# IR_remote.net
KiCad netlist of a schematic drawn in Altium Designer
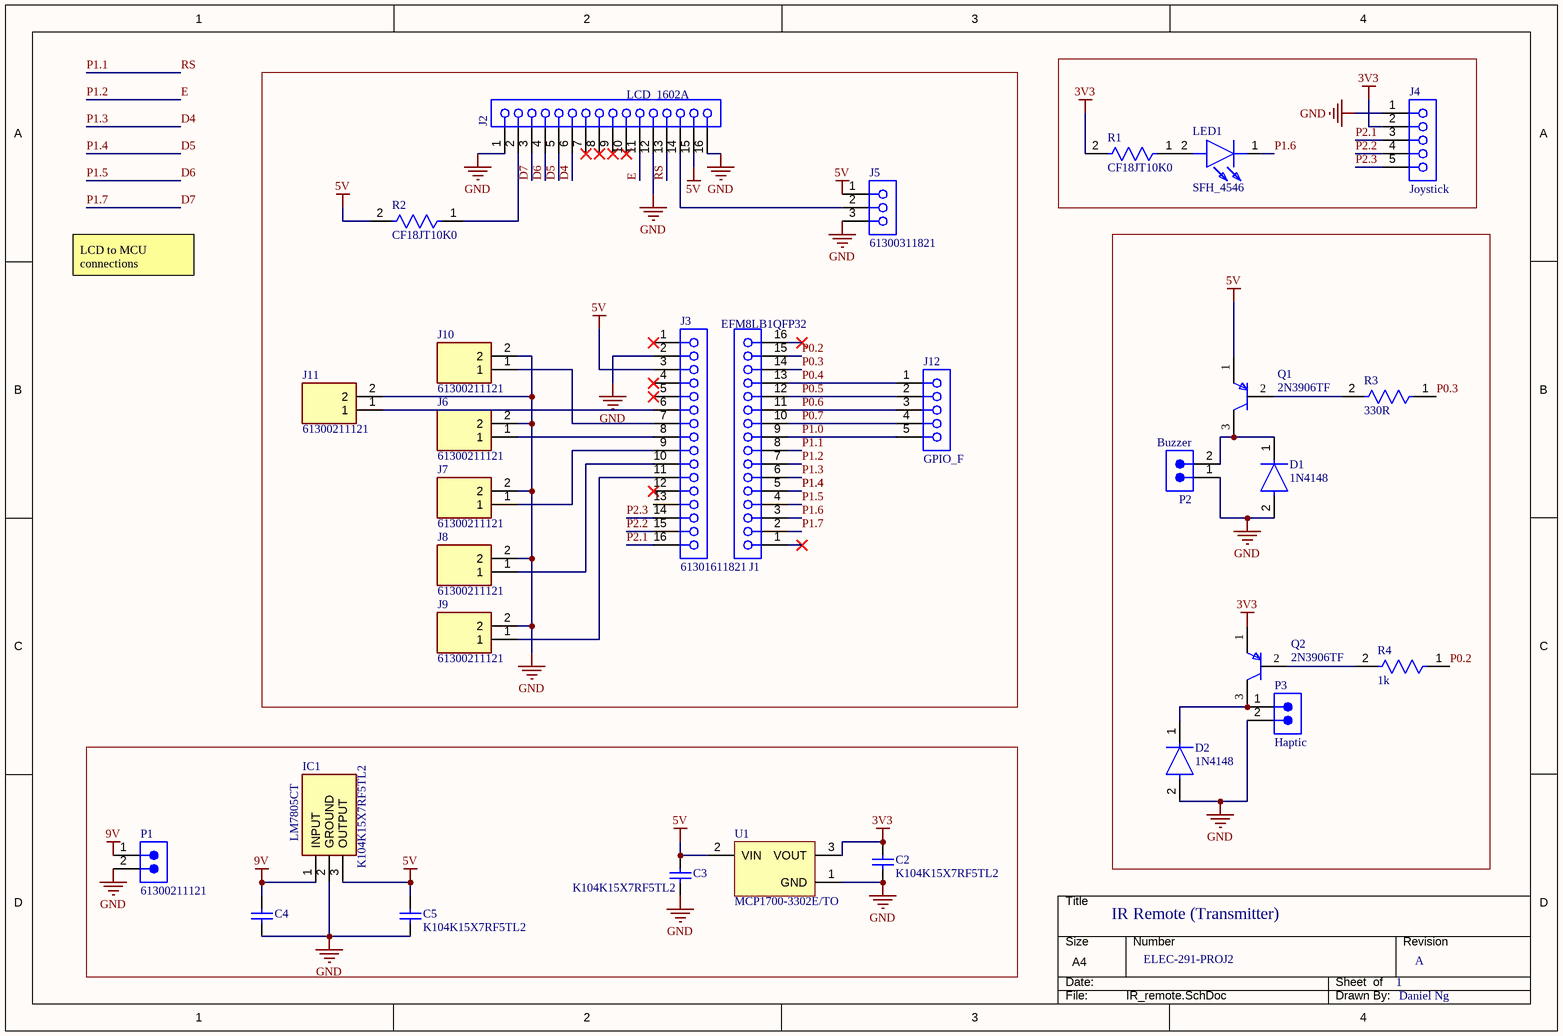
[diagram p0: IR_remote.SchDoc]

(export (version "E")
  (design (tool "Eeschema 10.0.6"))
  (components
    (comp (ref "C2")
      (value "K104K15X7RF5TL2")
      (footprint "VISH-K104K15X7RF5TL2")
      (description "Ceramic Capacitor, 100 nF, +/- 10%, 50 V, -55 to 125 degC, 2-Pin THD, RoHS, Tape and Reel")
      (fields (field (name "MANUFACTURER") "Vishay") (field (name "TOLERANCE") "±10%"))
      (libsource (lib "Altium Content Vault") (part "CAP-NP-2"))
    )
    (comp (ref "C3")
      (value "K104K15X7RF5TL2")
      (footprint "VISH-K104K15X7RF5TL2")
      (description "Ceramic Capacitor, 100 nF, +/- 10%, 50 V, -55 to 125 degC, 2-Pin THD, RoHS, Tape and Reel")
      (fields (field (name "MANUFACTURER") "Vishay") (field (name "TOLERANCE") "±10%"))
      (libsource (lib "Altium Content Vault") (part "CAP-NP-2"))
    )
    (comp (ref "C4")
      (value "K104K15X7RF5TL2")
      (footprint "VISH-K104K15X7RF5TL2")
      (description "Ceramic Capacitor, 100 nF, +/- 10%, 50 V, -55 to 125 degC, 2-Pin THD, RoHS, Tape and Reel")
      (fields (field (name "MANUFACTURER") "Vishay") (field (name "TOLERANCE") "±10%"))
      (libsource (lib "Altium Content Vault") (part "CAP-NP-2"))
    )
    (comp (ref "C5")
      (value "K104K15X7RF5TL2")
      (footprint "VISH-K104K15X7RF5TL2")
      (description "Ceramic Capacitor, 100 nF, +/- 10%, 50 V, -55 to 125 degC, 2-Pin THD, RoHS, Tape and Reel")
      (fields (field (name "MANUFACTURER") "Vishay") (field (name "TOLERANCE") "±10%"))
      (libsource (lib "Altium Content Vault") (part "CAP-NP-2"))
    )
    (comp (ref "D1")
      (value "1N4148")
      (footprint "FP-017AG-MFG")
      (description "DIODE GEN PURP 100V 200MA DO35")
      (fields (field (name "VOLTAGE") "100V"))
      (libsource (lib "Altium Content Vault") (part "d7152d700b627762746794eb795d46e"))
    )
    (comp (ref "D2")
      (value "1N4148")
      (footprint "FP-017AG-MFG")
      (description "DIODE GEN PURP 100V 200MA DO35")
      (fields (field (name "VOLTAGE") "100V"))
      (libsource (lib "Altium Content Vault") (part "d7152d700b627762746794eb795d46e"))
    )
    (comp (ref "IC1")
      (value "LM7805CT")
      (footprint "SamacSys:TO254P470X1028X1955-3P")
      (description "Integrated Circuit")
      (fields (field (name "MOUSER PART NUMBER") "926-LM7805CT"))
      (libsource (lib "*") (part "LM7805CT"))
    )
    (comp (ref "J1")
      (value "EFM8LB1QFP32")
      (footprint "61301611821")
      (description "THT Vertical Socket Header WR-PHD, Pitch 2.54 mm, Single Row, 16 pins")
      (libsource (lib "Altium Content Vault") (part "Header_Female_1R_16P"))
    )
    (comp (ref "J2")
      (value "LCD_1602A")
      (footprint "61301611821")
      (description "THT Vertical Socket Header WR-PHD, Pitch 2.54 mm, Single Row, 16 pins")
      (libsource (lib "Altium Content Vault") (part "Header_Female_1R_16P"))
    )
    (comp (ref "J3")
      (value "61301611821")
      (footprint "61301611821")
      (description "THT Vertical Socket Header WR-PHD, Pitch 2.54 mm, Single Row, 16 pins")
      (libsource (lib "Altium Content Vault") (part "Header_Female_1R_16P"))
    )
    (comp (ref "J4")
      (value "Joystick")
      (footprint "61300511821")
      (description "THT Vertical Socket Header WR-PHD, Pitch 2.54 mm, Single Row, 5 pins")
      (libsource (lib "Altium Content Vault") (part "Header_Female_1R_05P"))
    )
    (comp (ref "J5")
      (value "61300311821")
      (footprint "61300311821")
      (description "Btb Conn, Rcpt, 3Pos, 1Row, 2.54Mm Rohs Compliant: Yes")
      (libsource (lib "Altium Content Vault") (part "Header_Female_1R_03P"))
    )
    (comp (ref "J6")
      (value "61300211121")
      (footprint "SamacSys:HDRV2W110P0X254_1X2_508X254X854P")
      (description "Connector")
      (fields (field (name "MOUSER PART NUMBER") "710-61300211121"))
      (libsource (lib "*") (part "61300211121"))
    )
    (comp (ref "J7")
      (value "61300211121")
      (footprint "SamacSys:HDRV2W110P0X254_1X2_508X254X854P")
      (description "Connector")
      (fields (field (name "MOUSER PART NUMBER") "710-61300211121"))
      (libsource (lib "*") (part "61300211121"))
    )
    (comp (ref "J8")
      (value "61300211121")
      (footprint "SamacSys:HDRV2W110P0X254_1X2_508X254X854P")
      (description "Connector")
      (fields (field (name "MOUSER PART NUMBER") "710-61300211121"))
      (libsource (lib "*") (part "61300211121"))
    )
    (comp (ref "J9")
      (value "61300211121")
      (footprint "SamacSys:HDRV2W110P0X254_1X2_508X254X854P")
      (description "Connector")
      (fields (field (name "MOUSER PART NUMBER") "710-61300211121"))
      (libsource (lib "*") (part "61300211121"))
    )
    (comp (ref "J10")
      (value "61300211121")
      (footprint "SamacSys:HDRV2W110P0X254_1X2_508X254X854P")
      (description "Connector")
      (fields (field (name "MOUSER PART NUMBER") "710-61300211121"))
      (libsource (lib "*") (part "61300211121"))
    )
    (comp (ref "J11")
      (value "61300211121")
      (footprint "SamacSys:HDRV2W110P0X254_1X2_508X254X854P")
      (description "Connector")
      (fields (field (name "MOUSER PART NUMBER") "710-61300211121"))
      (libsource (lib "*") (part "61300211121"))
    )
    (comp (ref "J12")
      (value "GPIO_F")
      (footprint "61300511821")
      (description "THT Vertical Socket Header WR-PHD, Pitch 2.54 mm, Single Row, 5 pins")
      (libsource (lib "Altium Content Vault") (part "Header_Female_1R_05P"))
    )
    (comp (ref "LED1")
      (value "SFH_4546")
      (footprint "SamacSys:SFH_4556P")
      (description "LED")
      (fields
        (field (name "MANUFACTURER_PART_NUMBER") "SFH 4546")
        (field (name "MOUSER PART NUMBER") "720-SFH4546")
      )
      (libsource (lib "*") (part "SFH_4546"))
    )
    (comp (ref "P1")
      (value "61300211121")
      (footprint "61300211121")
      (description "THT Vertical Pin Header WR-PHD, Pitch 2.54 mm, Single Row, 2 pins")
      (libsource (lib "Altium Content Vault") (part "Header_Male_1R_02P"))
    )
    (comp (ref "P2")
      (value "Buzzer")
      (footprint "62000211121")
      (description "THT Vertical Pin Header WR-PHD, Pitch 2.00 mm, Single Row, 2 pins")
      (libsource (lib "Altium Content Vault") (part "Header_Male_1R_02P"))
    )
    (comp (ref "P3")
      (value "Haptic")
      (footprint "62000211121")
      (description "THT Vertical Pin Header WR-PHD, Pitch 2.00 mm, Single Row, 2 pins")
      (libsource (lib "Altium Content Vault") (part "Header_Male_1R_02P"))
    )
    (comp (ref "Q1")
      (value "2N3906TF")
      (footprint "FP-135AR-MFG")
      (description "2N3906TF Small Signal Bipolar Transistor, 0.2A I(C), 40V V(BR)CEO, 1-Element, PNP, Silicon, TO-92")
      (libsource (lib "Altium Content Vault") (part "40d2b7e180a7bcff784209620afba3e"))
    )
    (comp (ref "Q2")
      (value "2N3906TF")
      (footprint "FP-135AR-MFG")
      (description "2N3906TF Small Signal Bipolar Transistor, 0.2A I(C), 40V V(BR)CEO, 1-Element, PNP, Silicon, TO-92")
      (libsource (lib "Altium Content Vault") (part "40d2b7e180a7bcff784209620afba3e"))
    )
    (comp (ref "R1")
      (value "CF18JT10K0")
      (footprint "FP-CF18-MFG")
      (description "RES 10K OHM 1/8W 5% CF AXIAL")
      (fields
        (field (name "MANUFACTURER") "Stackpole Electronics")
        (field (name "OCTOPART") "https://octopart.com/cf18jt10k0-stackpole+electronics-19205642")
      )
      (libsource (lib "Altium Content Vault") (part "1029c3af85768c4190bb7ad29bc67b5"))
    )
    (comp (ref "R2")
      (value "CF18JT10K0")
      (footprint "FP-CF18-MFG")
      (description "RES 10K OHM 1/8W 5% CF AXIAL")
      (fields
        (field (name "MANUFACTURER") "Stackpole Electronics")
        (field (name "OCTOPART") "https://octopart.com/cf18jt10k0-stackpole+electronics-19205642")
      )
      (libsource (lib "Altium Content Vault") (part "1029c3af85768c4190bb7ad29bc67b5"))
    )
    (comp (ref "R3")
      (value "330R")
      (footprint "FP-CF18-MFG")
      (description "RES 10K OHM 1/8W 5% CF AXIAL")
      (fields
        (field (name "MANUFACTURER PART NUMBER") "CF18JT10K0")
        (field (name "MANUFACTURER") "Stackpole Electronics")
      )
      (libsource (lib "Altium Content Vault") (part "1029c3af85768c4190bb7ad29bc67b5"))
    )
    (comp (ref "R4")
      (value "1k")
      (footprint "FP-CF18-MFG")
      (description "RES 10K OHM 1/8W 5% CF AXIAL")
      (fields
        (field (name "MANUFACTURER PART NUMBER") "CF18JT10K0")
        (field (name "MANUFACTURER") "Stackpole Electronics")
      )
      (libsource (lib "Altium Content Vault") (part "1029c3af85768c4190bb7ad29bc67b5"))
    )
    (comp (ref "U1")
      (value "MCP1700-3302E/TO")
      (footprint "TO-92-TO3")
      (description "Low Quiescent Current LDO, 3-Pin TO-92, Extended TemperatureBAG")
      (libsource (lib "Altium Content Vault") (part "PM-LINEREG-MCP1700-IL3B"))
    )
  )
  (nets
    (net (code "1") (name "/D4") (class "Default")
      (node (ref "J1") (pin "6") (pinfunction "6_6") (pintype "passive"))
      (node (ref "J2") (pin "6") (pinfunction "6_6") (pintype "passive"))
    )
    (net (code "2") (name "/D5") (class "Default")
      (node (ref "J1") (pin "5") (pinfunction "5_5") (pintype "passive"))
      (node (ref "J2") (pin "5") (pinfunction "5_5") (pintype "passive"))
    )
    (net (code "3") (name "/D6") (class "Default")
      (node (ref "J1") (pin "4") (pinfunction "4_4") (pintype "passive"))
      (node (ref "J2") (pin "4") (pinfunction "4_4") (pintype "passive"))
    )
    (net (code "4") (name "/D7") (class "Default")
      (node (ref "J1") (pin "2") (pinfunction "2_2") (pintype "passive"))
      (node (ref "J2") (pin "3") (pinfunction "3_3") (pintype "passive"))
    )
    (net (code "5") (name "/E") (class "Default")
      (node (ref "J1") (pin "7") (pinfunction "7_7") (pintype "passive"))
      (node (ref "J2") (pin "11") (pinfunction "11_11") (pintype "passive"))
    )
    (net (code "6") (name "/P0.2") (class "Default")
      (node (ref "J1") (pin "15") (pinfunction "15_15") (pintype "passive"))
      (node (ref "R4") (pin "1") (pinfunction "1_1") (pintype "passive"))
    )
    (net (code "7") (name "/P0.3") (class "Default")
      (node (ref "J1") (pin "14") (pinfunction "14_14") (pintype "passive"))
      (node (ref "R3") (pin "1") (pinfunction "1_1") (pintype "passive"))
    )
    (net (code "8") (name "/P0.4") (class "Default")
      (node (ref "J1") (pin "13") (pinfunction "13_13") (pintype "passive"))
      (node (ref "J12") (pin "1") (pinfunction "1_1") (pintype "passive"))
    )
    (net (code "9") (name "/P0.5") (class "Default")
      (node (ref "J1") (pin "12") (pinfunction "12_12") (pintype "passive"))
      (node (ref "J12") (pin "2") (pinfunction "2_2") (pintype "passive"))
    )
    (net (code "10") (name "/P0.6") (class "Default")
      (node (ref "J1") (pin "11") (pinfunction "11_11") (pintype "passive"))
      (node (ref "J12") (pin "3") (pinfunction "3_3") (pintype "passive"))
    )
    (net (code "11") (name "/P0.7") (class "Default")
      (node (ref "J1") (pin "10") (pinfunction "10_10") (pintype "passive"))
      (node (ref "J12") (pin "4") (pinfunction "4_4") (pintype "passive"))
    )
    (net (code "12") (name "/P1.0") (class "Default")
      (node (ref "J1") (pin "9") (pinfunction "9_9") (pintype "passive"))
      (node (ref "J12") (pin "5") (pinfunction "5_5") (pintype "passive"))
    )
    (net (code "13") (name "/P1.1") (class "Default")
      (node (ref "J1") (pin "8") (pinfunction "8_8") (pintype "passive"))
      (node (ref "J2") (pin "13") (pinfunction "13_13") (pintype "passive"))
    )
    (net (code "14") (name "/P1.6") (class "Default")
      (node (ref "J1") (pin "3") (pinfunction "3_3") (pintype "passive"))
      (node (ref "LED1") (pin "1") (pinfunction "K_1") (pintype "passive"))
    )
    (net (code "15") (name "/P2.1") (class "Default")
      (node (ref "J3") (pin "16") (pinfunction "16_16") (pintype "passive"))
      (node (ref "J4") (pin "3") (pinfunction "3_3") (pintype "passive"))
    )
    (net (code "16") (name "/P2.2") (class "Default")
      (node (ref "J3") (pin "15") (pinfunction "15_15") (pintype "passive"))
      (node (ref "J4") (pin "4") (pinfunction "4_4") (pintype "passive"))
    )
    (net (code "17") (name "/P2.3") (class "Default")
      (node (ref "J3") (pin "14") (pinfunction "14_14") (pintype "passive"))
      (node (ref "J4") (pin "5") (pinfunction "5_5") (pintype "passive"))
    )
    (net (code "18") (name "3V3") (class "Default")
      (node (ref "C2") (pin "1") (pinfunction "1_1") (pintype "passive"))
      (node (ref "J4") (pin "2") (pinfunction "2_2") (pintype "passive"))
      (node (ref "Q2") (pin "1") (pinfunction "E_1") (pintype "passive"))
      (node (ref "R1") (pin "2") (pinfunction "2_2") (pintype "passive"))
      (node (ref "U1") (pin "3") (pinfunction "VOUT_3") (pintype "power_in"))
    )
    (net (code "19") (name "5V") (class "Default")
      (node (ref "C3") (pin "1") (pinfunction "1_1") (pintype "passive"))
      (node (ref "C5") (pin "2") (pinfunction "2_2") (pintype "passive"))
      (node (ref "IC1") (pin "3") (pinfunction "OUTPUT_3") (pintype "passive"))
      (node (ref "J2") (pin "15") (pinfunction "15_15") (pintype "passive"))
      (node (ref "J3") (pin "3") (pinfunction "3_3") (pintype "passive"))
      (node (ref "J5") (pin "1") (pinfunction "1_1") (pintype "passive"))
      (node (ref "Q1") (pin "1") (pinfunction "E_1") (pintype "passive"))
      (node (ref "R2") (pin "2") (pinfunction "2_2") (pintype "passive"))
      (node (ref "U1") (pin "2") (pinfunction "VIN_2") (pintype "power_in"))
    )
    (net (code "20") (name "9V") (class "Default")
      (node (ref "C4") (pin "2") (pinfunction "2_2") (pintype "passive"))
      (node (ref "IC1") (pin "1") (pinfunction "INPUT_1") (pintype "passive"))
      (node (ref "P1") (pin "1") (pinfunction "1_1") (pintype "passive"))
    )
    (net (code "21") (name "GND") (class "Default")
      (node (ref "C2") (pin "2") (pinfunction "2_2") (pintype "passive"))
      (node (ref "C3") (pin "2") (pinfunction "2_2") (pintype "passive"))
      (node (ref "C4") (pin "1") (pinfunction "1_1") (pintype "passive"))
      (node (ref "C5") (pin "1") (pinfunction "1_1") (pintype "passive"))
      (node (ref "D1") (pin "2") (pinfunction "A_2") (pintype "passive"))
      (node (ref "D2") (pin "2") (pinfunction "A_2") (pintype "passive"))
      (node (ref "IC1") (pin "2") (pinfunction "GROUND_2") (pintype "passive"))
      (node (ref "J10") (pin "2") (pinfunction "2_2") (pintype "passive"))
      (node (ref "J11") (pin "2") (pinfunction "2_2") (pintype "passive"))
      (node (ref "J2") (pin "1") (pinfunction "1_1") (pintype "passive"))
      (node (ref "J2") (pin "12") (pinfunction "12_12") (pintype "passive"))
      (node (ref "J2") (pin "16") (pinfunction "16_16") (pintype "passive"))
      (node (ref "J3") (pin "2") (pinfunction "2_2") (pintype "passive"))
      (node (ref "J4") (pin "1") (pinfunction "1_1") (pintype "passive"))
      (node (ref "J5") (pin "3") (pinfunction "3_3") (pintype "passive"))
      (node (ref "J6") (pin "2") (pinfunction "2_2") (pintype "passive"))
      (node (ref "J7") (pin "2") (pinfunction "2_2") (pintype "passive"))
      (node (ref "J8") (pin "2") (pinfunction "2_2") (pintype "passive"))
      (node (ref "J9") (pin "2") (pinfunction "2_2") (pintype "passive"))
      (node (ref "P1") (pin "2") (pinfunction "2_2") (pintype "passive"))
      (node (ref "P2") (pin "1") (pinfunction "1_1") (pintype "passive"))
      (node (ref "P3") (pin "2") (pinfunction "2_2") (pintype "passive"))
      (node (ref "U1") (pin "1") (pinfunction "GND_1") (pintype "power_in"))
    )
    (net (code "22") (name "Net-(D1-C)") (class "Default")
      (node (ref "D1") (pin "1") (pinfunction "C_1") (pintype "passive"))
      (node (ref "P2") (pin "2") (pinfunction "2_2") (pintype "passive"))
      (node (ref "Q1") (pin "3") (pinfunction "C_3") (pintype "passive"))
    )
    (net (code "23") (name "Net-(D2-C)") (class "Default")
      (node (ref "D2") (pin "1") (pinfunction "C_1") (pintype "passive"))
      (node (ref "P3") (pin "1") (pinfunction "1_1") (pintype "passive"))
      (node (ref "Q2") (pin "3") (pinfunction "C_3") (pintype "passive"))
    )
    (net (code "24") (name "Net-(J2-Pad2)") (class "Default")
      (node (ref "J2") (pin "2") (pinfunction "2_2") (pintype "passive"))
      (node (ref "R2") (pin "1") (pinfunction "1_1") (pintype "passive"))
    )
    (net (code "25") (name "Net-(J2-Pad14)") (class "Default")
      (node (ref "J2") (pin "14") (pinfunction "14_14") (pintype "passive"))
      (node (ref "J5") (pin "2") (pinfunction "2_2") (pintype "passive"))
    )
    (net (code "26") (name "Net-(J3-Pad8)") (class "Default")
      (node (ref "J3") (pin "8") (pinfunction "8_8") (pintype "passive"))
      (node (ref "J6") (pin "1") (pinfunction "1_1") (pintype "passive"))
    )
    (net (code "27") (name "Net-(J3-Pad9)") (class "Default")
      (node (ref "J3") (pin "9") (pinfunction "9_9") (pintype "passive"))
      (node (ref "J7") (pin "1") (pinfunction "1_1") (pintype "passive"))
    )
    (net (code "28") (name "Net-(J3-Pad10)") (class "Default")
      (node (ref "J3") (pin "10") (pinfunction "10_10") (pintype "passive"))
      (node (ref "J8") (pin "1") (pinfunction "1_1") (pintype "passive"))
    )
    (net (code "29") (name "Net-(J3-Pad11)") (class "Default")
      (node (ref "J3") (pin "11") (pinfunction "11_11") (pintype "passive"))
      (node (ref "J9") (pin "1") (pinfunction "1_1") (pintype "passive"))
    )
    (net (code "30") (name "Net-(J10-Pad1)") (class "Default")
      (node (ref "J10") (pin "1") (pinfunction "1_1") (pintype "passive"))
      (node (ref "J3") (pin "7") (pinfunction "7_7") (pintype "passive"))
    )
    (net (code "31") (name "Net-(J11-Pad1)") (class "Default")
      (node (ref "J11") (pin "1") (pinfunction "1_1") (pintype "passive"))
      (node (ref "J3") (pin "6") (pinfunction "6_6") (pintype "passive"))
    )
    (net (code "32") (name "Net-(LED1-A)") (class "Default")
      (node (ref "LED1") (pin "2") (pinfunction "A_2") (pintype "passive"))
      (node (ref "R1") (pin "1") (pinfunction "1_1") (pintype "passive"))
    )
    (net (code "33") (name "Net-(Q1-B)") (class "Default")
      (node (ref "Q1") (pin "2") (pinfunction "B_2") (pintype "passive"))
      (node (ref "R3") (pin "2") (pinfunction "2_2") (pintype "passive"))
    )
    (net (code "34") (name "Net-(Q2-B)") (class "Default")
      (node (ref "Q2") (pin "2") (pinfunction "B_2") (pintype "passive"))
      (node (ref "R4") (pin "2") (pinfunction "2_2") (pintype "passive"))
    )
    (net (code "35") (name "unconnected-(J1-Pad1)") (class "Default")
      (node (ref "J1") (pin "1") (pinfunction "1_1") (pintype "passive+no_connect"))
    )
    (net (code "36") (name "unconnected-(J1-Pad16)") (class "Default")
      (node (ref "J1") (pin "16") (pinfunction "16_16") (pintype "passive+no_connect"))
    )
    (net (code "37") (name "unconnected-(J2-Pad7)") (class "Default")
      (node (ref "J2") (pin "7") (pinfunction "7_7") (pintype "passive+no_connect"))
    )
    (net (code "38") (name "unconnected-(J2-Pad8)") (class "Default")
      (node (ref "J2") (pin "8") (pinfunction "8_8") (pintype "passive+no_connect"))
    )
    (net (code "39") (name "unconnected-(J2-Pad9)") (class "Default")
      (node (ref "J2") (pin "9") (pinfunction "9_9") (pintype "passive+no_connect"))
    )
    (net (code "40") (name "unconnected-(J2-Pad10)") (class "Default")
      (node (ref "J2") (pin "10") (pinfunction "10_10") (pintype "passive+no_connect"))
    )
    (net (code "41") (name "unconnected-(J3-Pad1)") (class "Default")
      (node (ref "J3") (pin "1") (pinfunction "1_1") (pintype "passive+no_connect"))
    )
    (net (code "42") (name "unconnected-(J3-Pad4)") (class "Default")
      (node (ref "J3") (pin "4") (pinfunction "4_4") (pintype "passive+no_connect"))
    )
    (net (code "43") (name "unconnected-(J3-Pad5)") (class "Default")
      (node (ref "J3") (pin "5") (pinfunction "5_5") (pintype "passive+no_connect"))
    )
    (net (code "44") (name "unconnected-(J3-Pad12)") (class "Default")
      (node (ref "J3") (pin "12") (pinfunction "12_12") (pintype "passive+no_connect"))
    )
    (net (code "45") (name "unconnected-(J3-Pad13)") (class "Default")
      (node (ref "J3") (pin "13") (pinfunction "13_13") (pintype "passive"))
    )
  )
)
